# Alim.net
KiCad netlist of a schematic drawn in Altium Designer
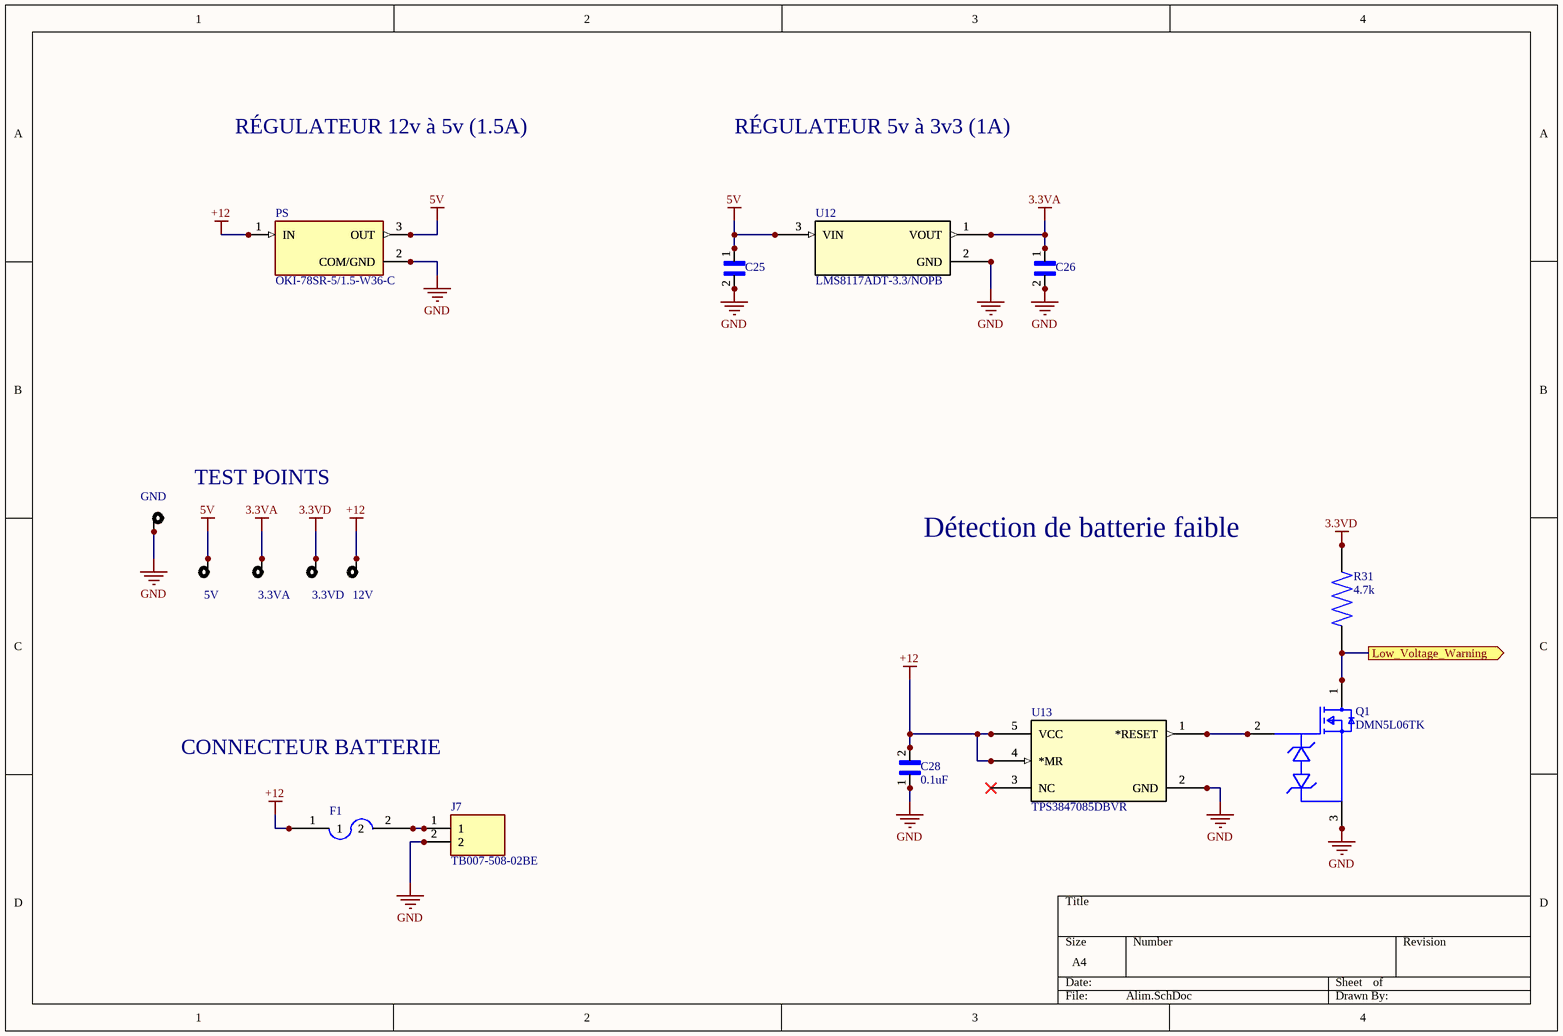
[diagram p0: Alim.SchDoc]

(export (version "E")
  (design (tool "Eeschema 10.0.6"))
  (components
    (comp (ref "3.3VA")
      (value "RCS-0C")
      (footprint "RCS-0C")
      (description "PC TEST POINT NATURAL")
      (libsource (lib "RCS-0C") (part "RCS-0C"))
    )
    (comp (ref "3.3VD")
      (value "RCS-0C")
      (footprint "RCS-0C")
      (description "PC TEST POINT NATURAL")
      (libsource (lib "RCS-0C") (part "RCS-0C"))
    )
    (comp (ref "5V")
      (value "RCS-0C")
      (footprint "RCS-0C")
      (description "PC TEST POINT NATURAL")
      (libsource (lib "RCS-0C") (part "RCS-0C"))
    )
    (comp (ref "12V")
      (value "RCS-0C")
      (footprint "RCS-0C")
      (description "PC TEST POINT NATURAL")
      (libsource (lib "RCS-0C") (part "RCS-0C"))
    )
    (comp (ref "C25")
      (value "TAJP106K010RNJ")
      (footprint "CAPC2012X140N")
      (description "TANTALUM CAPACITOR, 10UF, 10V, 0805 10%,")
      (libsource (lib "TAJP106K010RNJ") (part "TAJP106K010RNJ"))
    )
    (comp (ref "C26")
      (value "TAJP106K010RNJ")
      (footprint "CAPC2012X140N")
      (description "TANTALUM CAPACITOR, 10UF, 10V, 0805 10%,")
      (libsource (lib "TAJP106K010RNJ") (part "TAJP106K010RNJ"))
    )
    (comp (ref "C28")
      (value "0.1uF")
      (footprint "C3216C0G1H104J160AA")
      (fields (field (name "Comment") "C3216C0G1H104J160AA"))
      (libsource (lib "C3216C0G1H104J160AA") (part "C3216C0G1H104J160AA"))
    )
    (comp (ref "F1")
      (value "MF-SM150/33-2")
      (footprint "MF-SM150/33-2")
      (description "PTC RESET FUSE 33V 1.5A 2SMD")
      (libsource (lib "MF-SM150_33-2") (part "MF-SM150/33-2"))
    )
    (comp (ref "GND")
      (value "RCS-0C")
      (footprint "RCS-0C")
      (description "PC TEST POINT NATURAL")
      (libsource (lib "RCS-0C") (part "RCS-0C"))
    )
    (comp (ref "J7")
      (value "TB007-508-02BE")
      (footprint "CUI_TB007-508-02BE")
      (description "2~24 Poles, Screw Type, Horizontal, 5.08 Pitch, 24~12 _AWG_, Terminal Block Connector")
      (fields (field (name "MF") "CUI Devices"))
      (libsource (lib "TB007-508-02BE") (part "TB007-508-02BE"))
    )
    (comp (ref "PS")
      (value "OKI-78SR-5/1.5-W36-C")
      (footprint "CONV_OKI-78SR-5/1.5-W36-C")
      (description "Linear Regulator Replacement DC DC Converter 1 Output 5V 1.5A 7V - 36V Input")
      (fields (field (name "MF") "Murata Power"))
      (libsource (lib "OKI-78SR-5_1.5-W36-C") (part "OKI-78SR-5/1.5-W36-C"))
    )
    (comp (ref "Q1")
      (value "DMN5L06TK")
      (footprint "DMN5L06TK")
      (libsource (lib "DMN5L06TK") (part "DMN5L06TK"))
    )
    (comp (ref "R31")
      (value "4.7k")
      (footprint "CRGH0805F4K7")
      (description "CRGH0805 1% 4K7 0.33W")
      (fields (field (name "TOLERANCE") "±1%") (field (name "Comment") "CRGH0805F4K7"))
      (libsource (lib "CRGH0805F4K7") (part "CRGH0805F4K7"))
    )
    (comp (ref "U12")
      (value "LMS8117ADT-3.3/NOPB")
      (footprint "TD03B")
      (description "No Description Available")
      (fields
        (field (name "PARTNUMBER") "LMS8117ADT-33")
        (field (name "COPYRIGHT") "Copyright (C) 2021 Accelerated Designs. All rights reserved")
      )
      (libsource (lib "LMS8117ADT-3.3") (part "LMS8117ADT-3.3/NOPB"))
    )
    (comp (ref "U13")
      (value "TPS3847085DBVR")
      (footprint "DBV5_TEX-M")
      (description "No Description Available")
      (fields (field (name "COPYRIGHT") "Copyright (C) 2021 Accelerated Designs. All rights reserved"))
      (libsource (lib "TPS3847108DBVT") (part "TPS3847085DBVR"))
    )
  )
  (nets
    (net (code "1") (name "+12") (class "Default")
      (node (ref "12V") (pin "1") (pinfunction "1_1") (pintype "passive"))
      (node (ref "C28") (pin "2") (pinfunction "2_2") (pintype "passive"))
      (node (ref "F1") (pin "1") (pinfunction "1_1") (pintype "passive"))
      (node (ref "PS") (pin "1") (pinfunction "IN_1") (pintype "input"))
      (node (ref "U13") (pin "4") (pinfunction "*MR_4") (pintype "input"))
      (node (ref "U13") (pin "5") (pinfunction "VCC_5") (pintype "power_in"))
    )
    (net (code "2") (name "/Low_Voltage_Warning") (class "Default")
      (node (ref "Q1") (pin "1") (pinfunction "D_1") (pintype "passive"))
      (node (ref "R31") (pin "1") (pinfunction "1_1") (pintype "passive"))
    )
    (net (code "3") (name "3.3VA") (class "Default")
      (node (ref "3.3VA") (pin "1") (pinfunction "1_1") (pintype "passive"))
      (node (ref "C26") (pin "1") (pinfunction "1_1") (pintype "passive"))
      (node (ref "U12") (pin "1") (pinfunction "VOUT_1") (pintype "output"))
    )
    (net (code "4") (name "3.3VD") (class "Default")
      (node (ref "3.3VD") (pin "1") (pinfunction "1_1") (pintype "passive"))
      (node (ref "R31") (pin "2") (pinfunction "2_2") (pintype "passive"))
    )
    (net (code "5") (name "5V") (class "Default")
      (node (ref "5V") (pin "1") (pinfunction "1_1") (pintype "passive"))
      (node (ref "C25") (pin "1") (pinfunction "1_1") (pintype "passive"))
      (node (ref "PS") (pin "3") (pinfunction "OUT_3") (pintype "output"))
      (node (ref "U12") (pin "3") (pinfunction "VIN_3") (pintype "input"))
    )
    (net (code "6") (name "GND") (class "Default")
      (node (ref "C25") (pin "2") (pinfunction "2_2") (pintype "passive"))
      (node (ref "C26") (pin "2") (pinfunction "2_2") (pintype "passive"))
      (node (ref "C28") (pin "1") (pinfunction "1_1") (pintype "passive"))
      (node (ref "GND") (pin "1") (pinfunction "1_1") (pintype "passive"))
      (node (ref "J7") (pin "2") (pinfunction "2_2") (pintype "passive"))
      (node (ref "PS") (pin "2") (pinfunction "COM/GND_2") (pintype "power_in"))
      (node (ref "Q1") (pin "3") (pinfunction "S_3") (pintype "passive"))
      (node (ref "U12") (pin "2") (pinfunction "GND_2") (pintype "passive"))
      (node (ref "U13") (pin "2") (pinfunction "GND_2") (pintype "power_in"))
    )
    (net (code "7") (name "Net-(F1-Pad2)") (class "Default")
      (node (ref "F1") (pin "2") (pinfunction "2_2") (pintype "passive"))
      (node (ref "J7") (pin "1") (pinfunction "1_1") (pintype "passive"))
    )
    (net (code "8") (name "Net-(Q1-G)") (class "Default")
      (node (ref "Q1") (pin "2") (pinfunction "G_2") (pintype "passive"))
      (node (ref "U13") (pin "1") (pinfunction "*RESET_1") (pintype "output"))
    )
    (net (code "9") (name "unconnected-(U13-NC-Pad3)") (class "Default")
      (node (ref "U13") (pin "3") (pinfunction "NC_3") (pintype "passive+no_connect"))
    )
  )
)
